# Div4RX5808-PRO_MB_V1_2.net
KiCad netlist of a schematic drawn in EAGLE
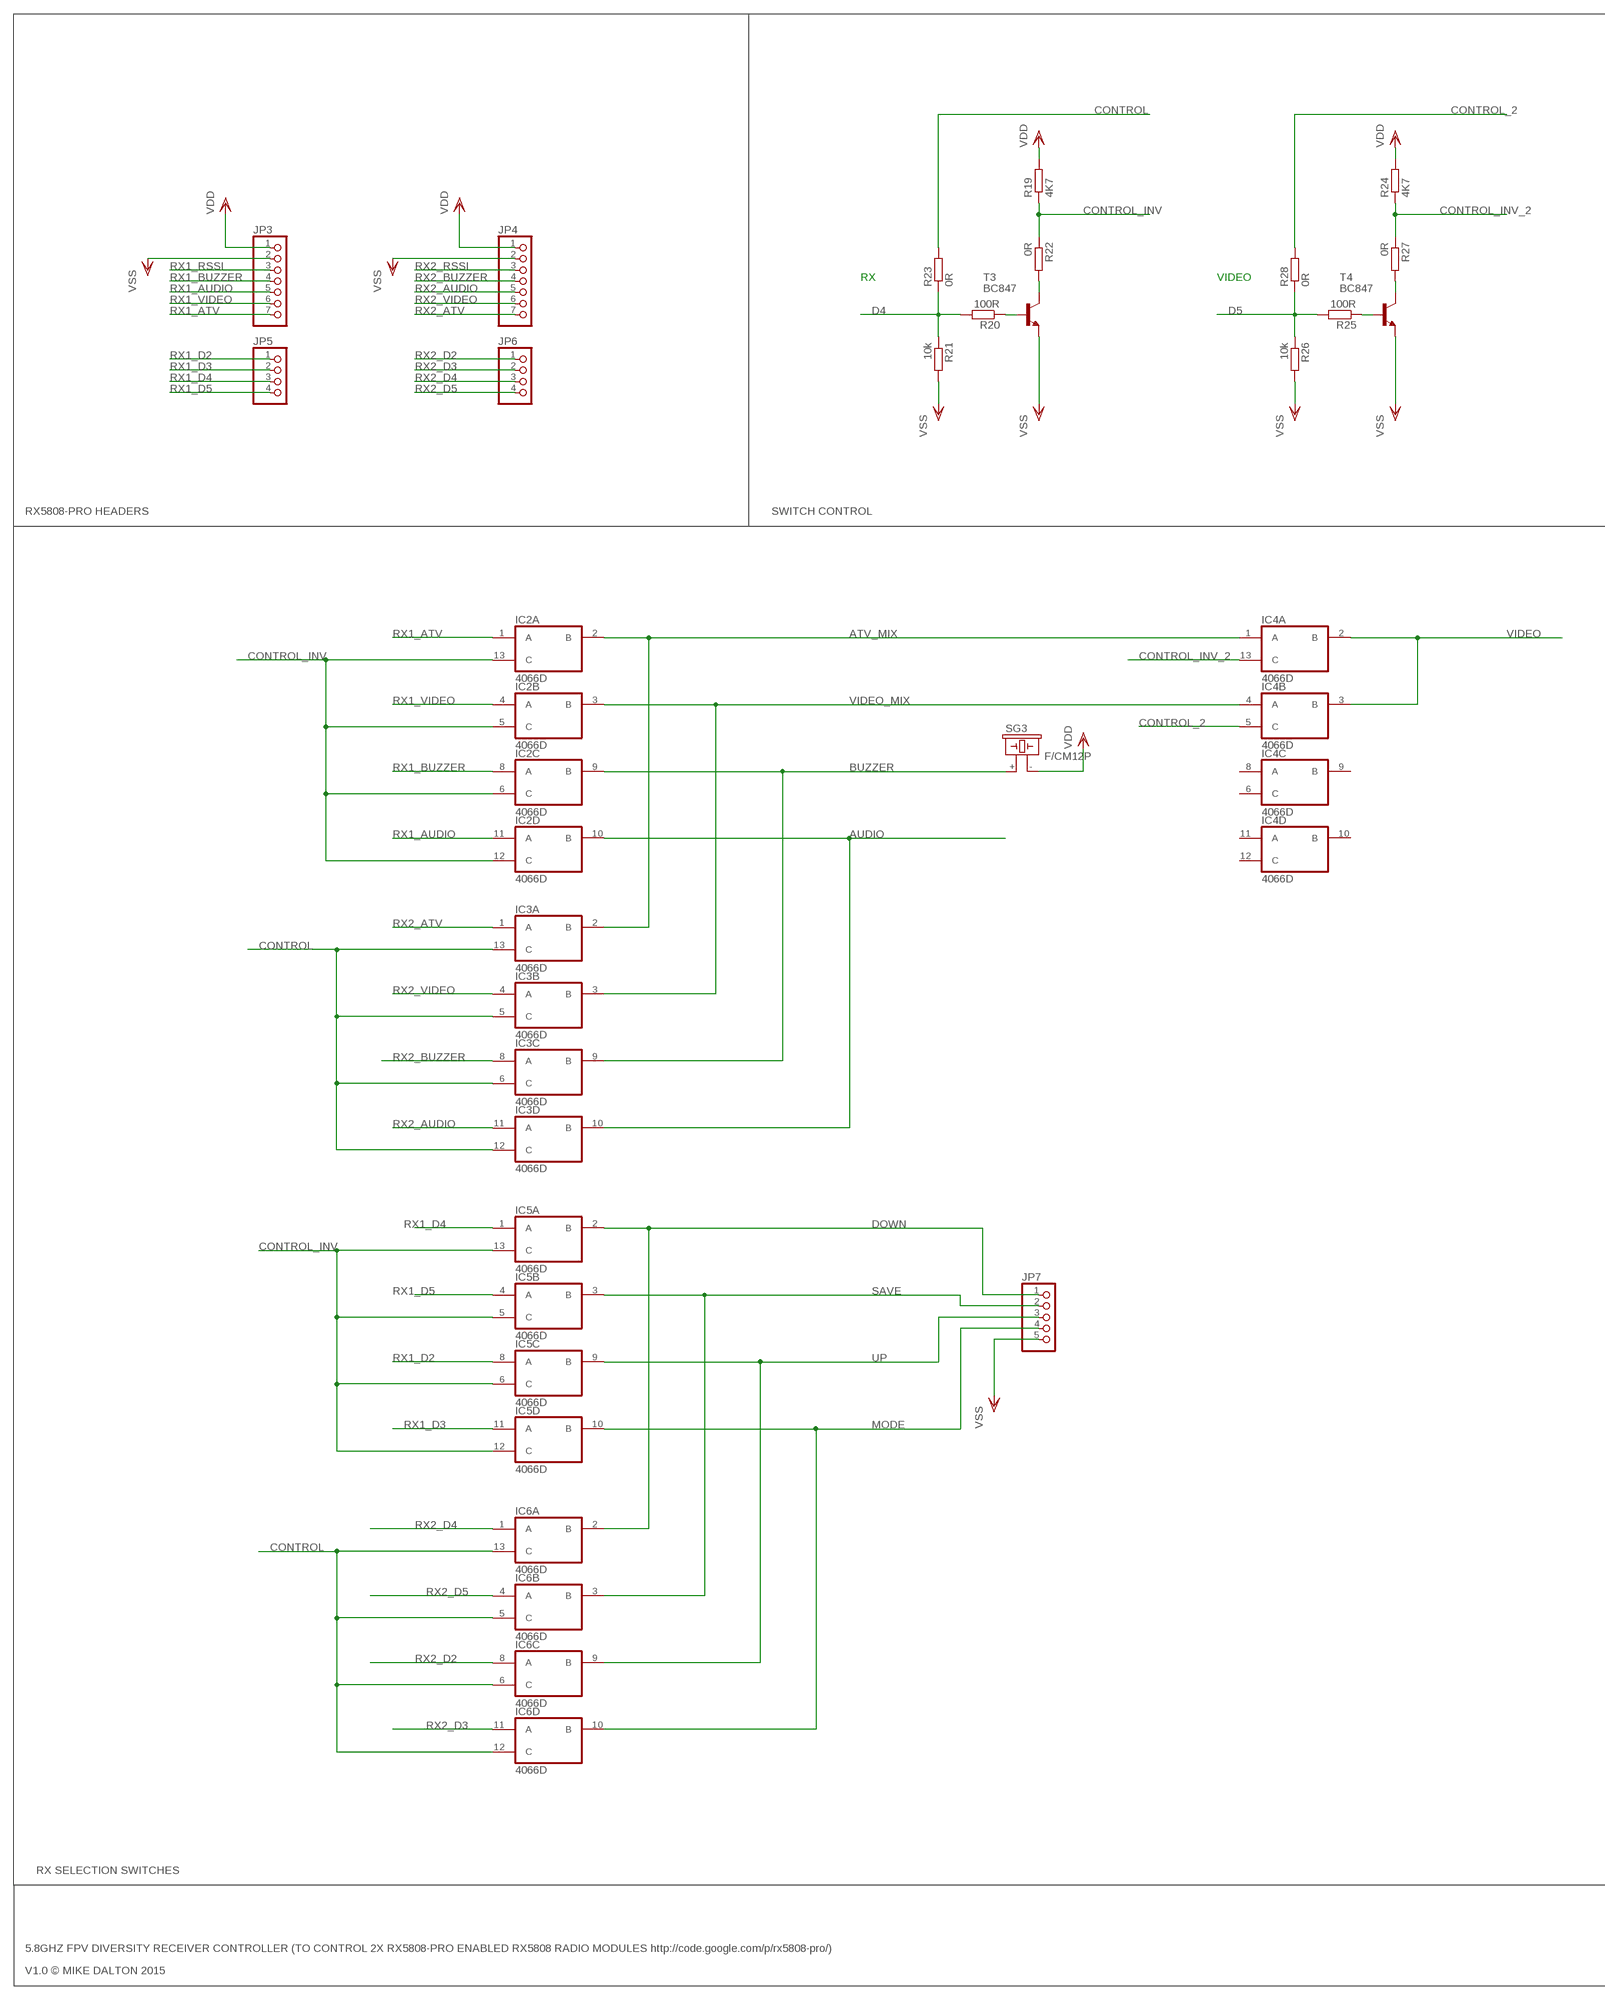
[diagram p0: schematic, sheet 1, part 1 of 2]
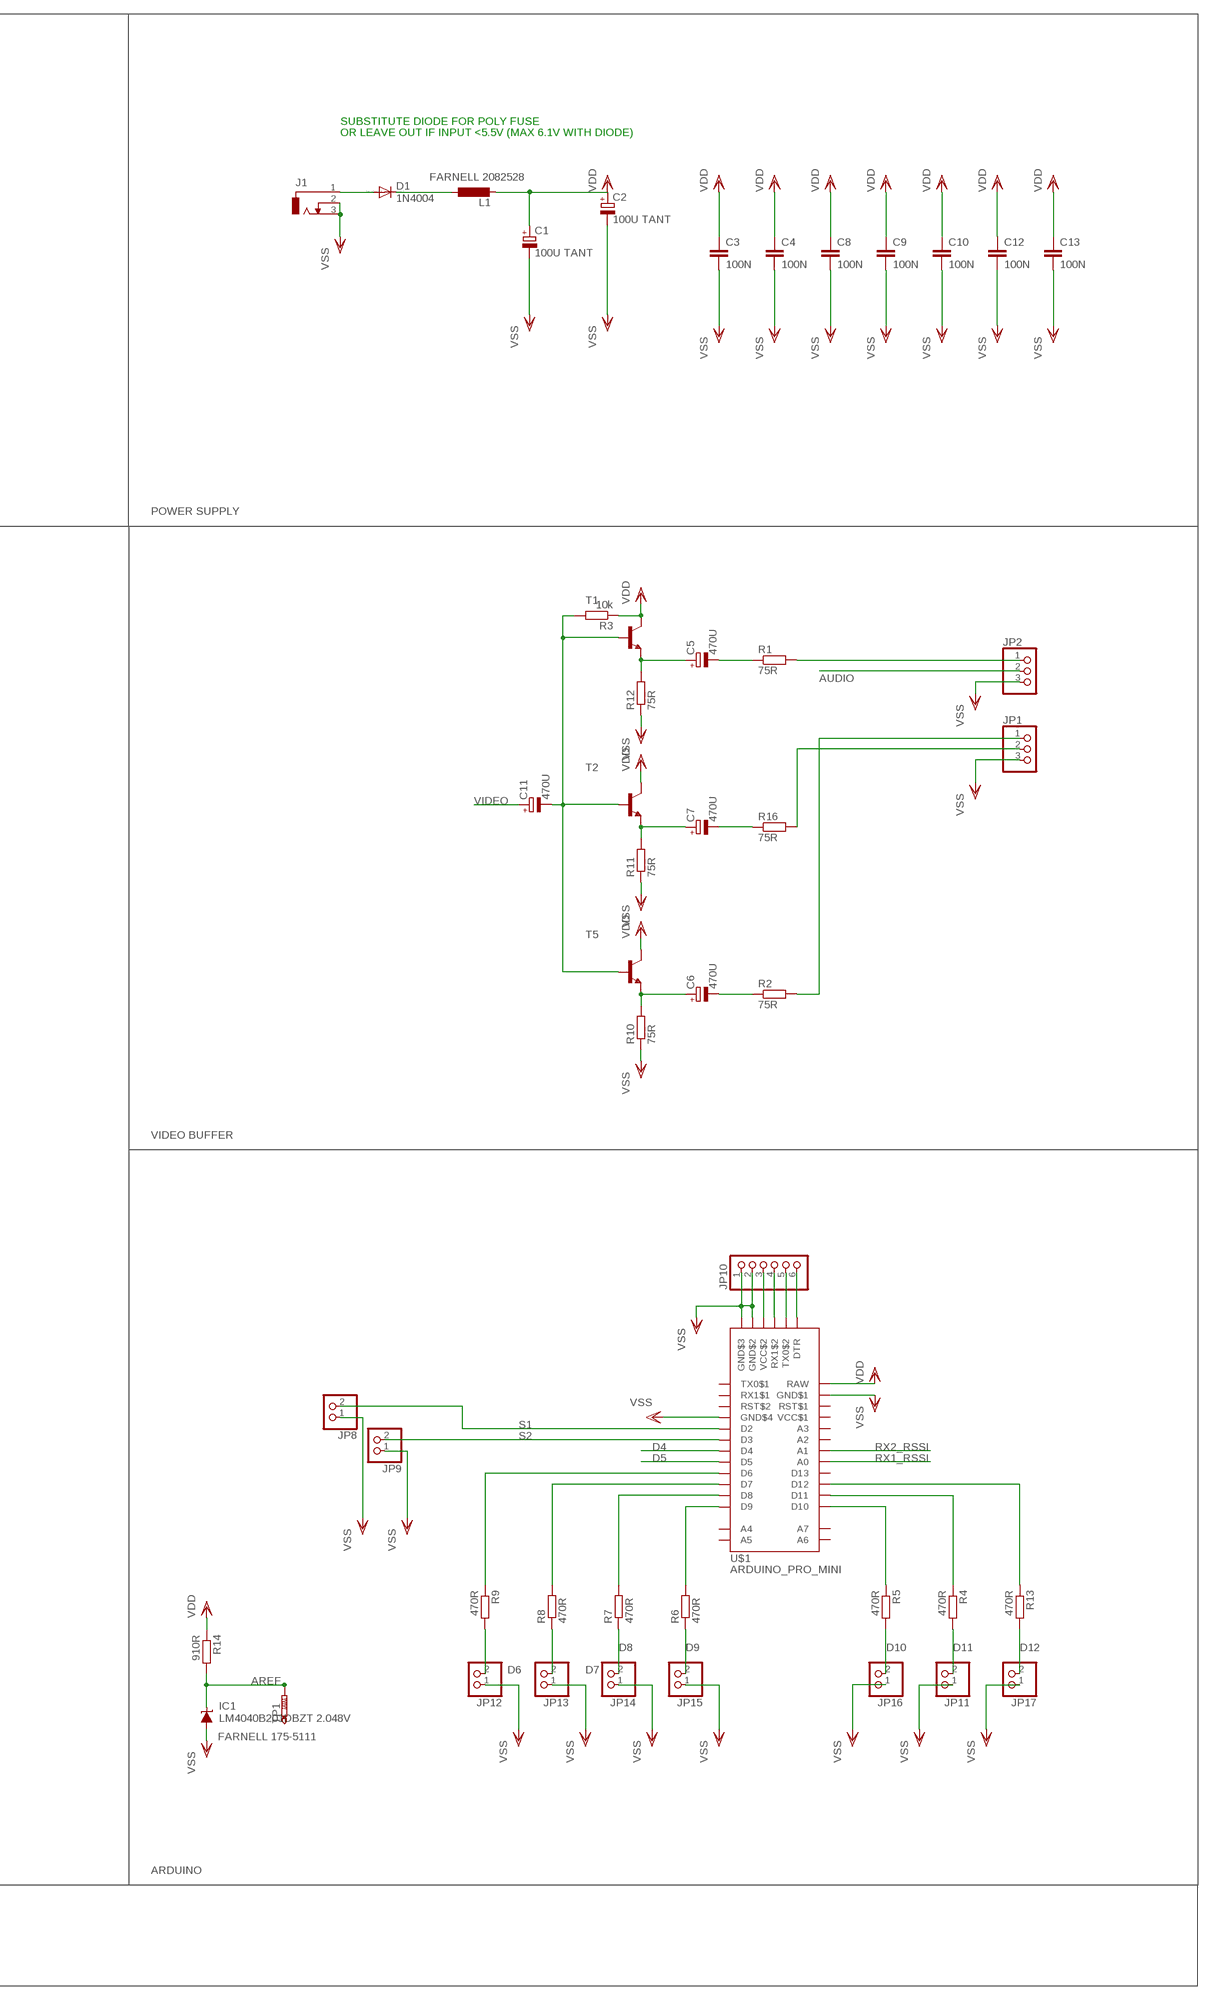
[diagram p1: schematic, sheet 1, part 2 of 2]

(export (version "E")
  (design (tool "Eeschema 10.0.6"))
  (components
    (comp (ref "C1")
      (value "100U TANT")
      (footprint "eagle-import:C_6032-28R")
      (libsource (lib "eagle-import") (part "CPOL-EUC/6032-28R"))
    )
    (comp (ref "C2")
      (value "100U TANT")
      (footprint "eagle-import:C_6032-28R")
      (libsource (lib "eagle-import") (part "CPOL-EUC/6032-28R"))
    )
    (comp (ref "C3")
      (value "100N")
      (footprint "eagle-import:C0603")
      (libsource (lib "eagle-import") (part "C-EUC0603"))
    )
    (comp (ref "C4")
      (value "100N")
      (footprint "eagle-import:C0603")
      (libsource (lib "eagle-import") (part "C-EUC0603"))
    )
    (comp (ref "C5")
      (value "470U")
      (footprint "eagle-import:E5-10,5")
      (libsource (lib "eagle-import") (part "CPOL-EUE5-10.5"))
    )
    (comp (ref "C6")
      (value "470U")
      (footprint "eagle-import:E5-10,5")
      (libsource (lib "eagle-import") (part "CPOL-EUE5-10.5"))
    )
    (comp (ref "C7")
      (value "470U")
      (footprint "eagle-import:E5-10,5")
      (libsource (lib "eagle-import") (part "CPOL-EUE5-10.5"))
    )
    (comp (ref "C8")
      (value "100N")
      (footprint "eagle-import:C0603")
      (libsource (lib "eagle-import") (part "C-EUC0603"))
    )
    (comp (ref "C9")
      (value "100N")
      (footprint "eagle-import:C0603")
      (libsource (lib "eagle-import") (part "C-EUC0603"))
    )
    (comp (ref "C10")
      (value "100N")
      (footprint "eagle-import:C0603")
      (libsource (lib "eagle-import") (part "C-EUC0603"))
    )
    (comp (ref "C11")
      (value "470U")
      (footprint "eagle-import:E5-10,5")
      (libsource (lib "eagle-import") (part "CPOL-EUE5-10.5"))
    )
    (comp (ref "C12")
      (value "100N")
      (footprint "eagle-import:C0603")
      (libsource (lib "eagle-import") (part "C-EUC0603"))
    )
    (comp (ref "C13")
      (value "100N")
      (footprint "eagle-import:C0603")
      (libsource (lib "eagle-import") (part "C-EUC0603"))
    )
    (comp (ref "D1")
      (value "1N4004")
      (footprint "eagle-import:DO41-10")
      (libsource (lib "eagle-import") (part "1N4004"))
    )
    (comp (ref "IC1")
      (value "LM4040B201DBZT 2.048V")
      (footprint "eagle-import:DBZ_R-PDSO-G3")
      (fields (field (name "MPN") "LM4041A12IDBZR"))
      (libsource (lib "eagle-import") (part "LM4041DBZA12"))
    )
    (comp (ref "IC2")
      (value "4066D")
      (footprint "eagle-import:SO14")
      (libsource (lib "eagle-import") (part "4066D"))
    )
    (comp (ref "IC3")
      (value "4066D")
      (footprint "eagle-import:SO14")
      (libsource (lib "eagle-import") (part "4066D"))
    )
    (comp (ref "IC4")
      (value "4066D")
      (footprint "eagle-import:SO14")
      (libsource (lib "eagle-import") (part "4066D"))
    )
    (comp (ref "IC5")
      (value "4066D")
      (footprint "eagle-import:SO14")
      (libsource (lib "eagle-import") (part "4066D"))
    )
    (comp (ref "IC6")
      (value "4066D")
      (footprint "eagle-import:SO14")
      (libsource (lib "eagle-import") (part "4066D"))
    )
    (comp (ref "J1")
      (value "DCJ0303")
      (footprint "eagle-import:DCJ0303")
      (libsource (lib "eagle-import") (part "DCJ0303"))
    )
    (comp (ref "JP1")
      (value "PINHD-1X3")
      (footprint "eagle-import:1X03")
      (libsource (lib "eagle-import") (part "PINHD-1X3"))
    )
    (comp (ref "JP2")
      (value "PINHD-1X3")
      (footprint "eagle-import:1X03")
      (libsource (lib "eagle-import") (part "PINHD-1X3"))
    )
    (comp (ref "JP3")
      (value "PINHD-1X7")
      (footprint "eagle-import:1X07")
      (libsource (lib "eagle-import") (part "PINHD-1X7"))
    )
    (comp (ref "JP4")
      (value "PINHD-1X7")
      (footprint "eagle-import:1X07")
      (libsource (lib "eagle-import") (part "PINHD-1X7"))
    )
    (comp (ref "JP5")
      (value "PINHD-1X4")
      (footprint "eagle-import:1X04")
      (libsource (lib "eagle-import") (part "PINHD-1X4"))
    )
    (comp (ref "JP6")
      (value "PINHD-1X4")
      (footprint "eagle-import:1X04")
      (libsource (lib "eagle-import") (part "PINHD-1X4"))
    )
    (comp (ref "JP7")
      (value "PINHD-1X5")
      (footprint "eagle-import:1X05")
      (libsource (lib "eagle-import") (part "PINHD-1X5"))
    )
    (comp (ref "JP8")
      (value "PINHD-1X2")
      (footprint "eagle-import:1X02")
      (libsource (lib "eagle-import") (part "PINHD-1X2"))
    )
    (comp (ref "JP9")
      (value "PINHD-1X2")
      (footprint "eagle-import:1X02")
      (libsource (lib "eagle-import") (part "PINHD-1X2"))
    )
    (comp (ref "JP10")
      (value "PINHD-1X6")
      (footprint "eagle-import:1X06")
      (libsource (lib "eagle-import") (part "PINHD-1X6"))
    )
    (comp (ref "JP11")
      (value "PINHD-1X2")
      (footprint "eagle-import:1X02")
      (libsource (lib "eagle-import") (part "PINHD-1X2"))
    )
    (comp (ref "JP12")
      (value "PINHD-1X2")
      (footprint "eagle-import:1X02")
      (libsource (lib "eagle-import") (part "PINHD-1X2"))
    )
    (comp (ref "JP13")
      (value "PINHD-1X2")
      (footprint "eagle-import:1X02")
      (libsource (lib "eagle-import") (part "PINHD-1X2"))
    )
    (comp (ref "JP14")
      (value "PINHD-1X2")
      (footprint "eagle-import:1X02")
      (libsource (lib "eagle-import") (part "PINHD-1X2"))
    )
    (comp (ref "JP15")
      (value "PINHD-1X2")
      (footprint "eagle-import:1X02")
      (libsource (lib "eagle-import") (part "PINHD-1X2"))
    )
    (comp (ref "JP16")
      (value "PINHD-1X2")
      (footprint "eagle-import:1X02")
      (libsource (lib "eagle-import") (part "PINHD-1X2"))
    )
    (comp (ref "JP17")
      (value "PINHD-1X2")
      (footprint "eagle-import:1X02")
      (libsource (lib "eagle-import") (part "PINHD-1X2"))
    )
    (comp (ref "L1")
      (value "L-EU0207/7")
      (footprint "eagle-import:0207_7")
      (libsource (lib "eagle-import") (part "L-EU0207/7"))
    )
    (comp (ref "R1")
      (value "75R")
      (footprint "eagle-import:M0805")
      (libsource (lib "eagle-import") (part "R-EU_M0805"))
    )
    (comp (ref "R2")
      (value "75R")
      (footprint "eagle-import:M0805")
      (libsource (lib "eagle-import") (part "R-EU_M0805"))
    )
    (comp (ref "R3")
      (value "10k")
      (footprint "eagle-import:M0805")
      (libsource (lib "eagle-import") (part "R-EU_M0805"))
    )
    (comp (ref "R4")
      (value "470R")
      (footprint "eagle-import:R0603")
      (libsource (lib "eagle-import") (part "R-EU_R0603"))
    )
    (comp (ref "R5")
      (value "470R")
      (footprint "eagle-import:R0603")
      (libsource (lib "eagle-import") (part "R-EU_R0603"))
    )
    (comp (ref "R6")
      (value "470R")
      (footprint "eagle-import:R0603")
      (libsource (lib "eagle-import") (part "R-EU_R0603"))
    )
    (comp (ref "R7")
      (value "470R")
      (footprint "eagle-import:R0603")
      (libsource (lib "eagle-import") (part "R-EU_R0603"))
    )
    (comp (ref "R8")
      (value "470R")
      (footprint "eagle-import:R0603")
      (libsource (lib "eagle-import") (part "R-EU_R0603"))
    )
    (comp (ref "R9")
      (value "470R")
      (footprint "eagle-import:R0603")
      (libsource (lib "eagle-import") (part "R-EU_R0603"))
    )
    (comp (ref "R10")
      (value "75R")
      (footprint "eagle-import:M0805")
      (libsource (lib "eagle-import") (part "R-EU_M0805"))
    )
    (comp (ref "R11")
      (value "75R")
      (footprint "eagle-import:M0805")
      (libsource (lib "eagle-import") (part "R-EU_M0805"))
    )
    (comp (ref "R12")
      (value "75R")
      (footprint "eagle-import:M0805")
      (libsource (lib "eagle-import") (part "R-EU_M0805"))
    )
    (comp (ref "R13")
      (value "470R")
      (footprint "eagle-import:R0603")
      (libsource (lib "eagle-import") (part "R-EU_R0603"))
    )
    (comp (ref "R14")
      (value "910R")
      (footprint "eagle-import:R0603")
      (libsource (lib "eagle-import") (part "R-EU_R0603"))
    )
    (comp (ref "R16")
      (value "75R")
      (footprint "eagle-import:M0805")
      (libsource (lib "eagle-import") (part "R-EU_M0805"))
    )
    (comp (ref "R19")
      (value "4K7")
      (footprint "eagle-import:M0805")
      (libsource (lib "eagle-import") (part "R-EU_M0805"))
    )
    (comp (ref "R20")
      (value "100R")
      (footprint "eagle-import:M0805")
      (libsource (lib "eagle-import") (part "R-EU_M0805"))
    )
    (comp (ref "R21")
      (value "10k")
      (footprint "eagle-import:M0805")
      (libsource (lib "eagle-import") (part "R-EU_M0805"))
    )
    (comp (ref "R22")
      (value "0R")
      (footprint "eagle-import:M0805")
      (libsource (lib "eagle-import") (part "R-EU_M0805"))
    )
    (comp (ref "R23")
      (value "0R")
      (footprint "eagle-import:M0805")
      (libsource (lib "eagle-import") (part "R-EU_M0805"))
    )
    (comp (ref "R24")
      (value "4K7")
      (footprint "eagle-import:M0805")
      (libsource (lib "eagle-import") (part "R-EU_M0805"))
    )
    (comp (ref "R25")
      (value "100R")
      (footprint "eagle-import:M0805")
      (libsource (lib "eagle-import") (part "R-EU_M0805"))
    )
    (comp (ref "R26")
      (value "10k")
      (footprint "eagle-import:M0805")
      (libsource (lib "eagle-import") (part "R-EU_M0805"))
    )
    (comp (ref "R27")
      (value "0R")
      (footprint "eagle-import:M0805")
      (libsource (lib "eagle-import") (part "R-EU_M0805"))
    )
    (comp (ref "R28")
      (value "0R")
      (footprint "eagle-import:M0805")
      (libsource (lib "eagle-import") (part "R-EU_M0805"))
    )
    (comp (ref "SG3")
      (value "F/CM12P")
      (footprint "eagle-import:F_CM12P")
      (libsource (lib "eagle-import") (part "F/CM12P"))
    )
    (comp (ref "T1")
      (value "MMBT2222ALT1-NPN-SOT23-BEC")
      (footprint "eagle-import:SOT23-BEC")
      (libsource (lib "eagle-import") (part "transistor-neu-to92_-NPN-SOT23-BECMMBT2222ALT1"))
    )
    (comp (ref "T2")
      (value "MMBT2222ALT1-NPN-SOT23-BEC")
      (footprint "eagle-import:SOT23-BEC")
      (libsource (lib "eagle-import") (part "transistor-neu-to92_-NPN-SOT23-BECMMBT2222ALT1"))
    )
    (comp (ref "T3")
      (value "BC847")
      (footprint "eagle-import:SOT23-BEC")
      (libsource (lib "eagle-import") (part "-NPN-SOT23-BECBC847B"))
    )
    (comp (ref "T4")
      (value "BC847")
      (footprint "eagle-import:SOT23-BEC")
      (libsource (lib "eagle-import") (part "-NPN-SOT23-BECBC847B"))
    )
    (comp (ref "T5")
      (value "MMBT2222ALT1-NPN-SOT23-BEC")
      (footprint "eagle-import:SOT23-BEC")
      (libsource (lib "eagle-import") (part "transistor-neu-to92_-NPN-SOT23-BECMMBT2222ALT1"))
    )
    (comp (ref "TP1")
      (value "PTR1TP20SQ")
      (footprint "eagle-import:TP20SQ")
      (libsource (lib "eagle-import") (part "PTR1TP20SQ"))
    )
    (comp (ref "U$1")
      (value "ARDUINO_PRO_MINI")
      (footprint "eagle-import:ARDUINO_PRO_MINI")
      (libsource (lib "eagle-import") (part "ARDUINO_PRO_MINI"))
    )
  )
  (nets
    (net (code "1") (name "/AREF") (class "Default")
      (node (ref "IC1") (pin "1") (pinfunction "C_1") (pintype "passive"))
      (node (ref "R14") (pin "2") (pinfunction "2_2") (pintype "passive"))
      (node (ref "TP1") (pin "TP") (pinfunction "TP_TP") (pintype "input"))
    )
    (net (code "2") (name "/ATV_MIX") (class "Default")
      (node (ref "IC2") (pin "2") (pinfunction "B_2") (pintype "tri_state"))
      (node (ref "IC3") (pin "2") (pinfunction "B_2") (pintype "tri_state"))
      (node (ref "IC4") (pin "1") (pinfunction "A_1") (pintype "tri_state"))
    )
    (net (code "3") (name "/AUDIO") (class "Default")
      (node (ref "IC2") (pin "10") (pinfunction "B_10") (pintype "tri_state"))
      (node (ref "IC3") (pin "10") (pinfunction "B_10") (pintype "tri_state"))
      (node (ref "JP2") (pin "2") (pinfunction "2_2") (pintype "passive"))
    )
    (net (code "4") (name "/BUZZER") (class "Default")
      (node (ref "IC2") (pin "9") (pinfunction "B_9") (pintype "tri_state"))
      (node (ref "IC3") (pin "9") (pinfunction "B_9") (pintype "tri_state"))
      (node (ref "SG3") (pin "+") (pinfunction "1_+") (pintype "passive"))
    )
    (net (code "5") (name "/CONTROL") (class "Default")
      (node (ref "IC3") (pin "12") (pinfunction "C_12") (pintype "input"))
      (node (ref "IC3") (pin "13") (pinfunction "C_13") (pintype "input"))
      (node (ref "IC3") (pin "5") (pinfunction "C_5") (pintype "input"))
      (node (ref "IC3") (pin "6") (pinfunction "C_6") (pintype "input"))
      (node (ref "IC6") (pin "12") (pinfunction "C_12") (pintype "input"))
      (node (ref "IC6") (pin "13") (pinfunction "C_13") (pintype "input"))
      (node (ref "IC6") (pin "5") (pinfunction "C_5") (pintype "input"))
      (node (ref "IC6") (pin "6") (pinfunction "C_6") (pintype "input"))
      (node (ref "R23") (pin "2") (pinfunction "2_2") (pintype "passive"))
    )
    (net (code "6") (name "/CONTROL_2") (class "Default")
      (node (ref "IC4") (pin "5") (pinfunction "C_5") (pintype "input"))
      (node (ref "R28") (pin "2") (pinfunction "2_2") (pintype "passive"))
    )
    (net (code "7") (name "/CONTROL_INV") (class "Default")
      (node (ref "IC2") (pin "12") (pinfunction "C_12") (pintype "input"))
      (node (ref "IC2") (pin "13") (pinfunction "C_13") (pintype "input"))
      (node (ref "IC2") (pin "5") (pinfunction "C_5") (pintype "input"))
      (node (ref "IC2") (pin "6") (pinfunction "C_6") (pintype "input"))
      (node (ref "IC5") (pin "12") (pinfunction "C_12") (pintype "input"))
      (node (ref "IC5") (pin "13") (pinfunction "C_13") (pintype "input"))
      (node (ref "IC5") (pin "5") (pinfunction "C_5") (pintype "input"))
      (node (ref "IC5") (pin "6") (pinfunction "C_6") (pintype "input"))
      (node (ref "R19") (pin "1") (pinfunction "1_1") (pintype "passive"))
      (node (ref "R22") (pin "1") (pinfunction "1_1") (pintype "passive"))
    )
    (net (code "8") (name "/CONTROL_INV_2") (class "Default")
      (node (ref "IC4") (pin "13") (pinfunction "C_13") (pintype "input"))
      (node (ref "R24") (pin "1") (pinfunction "1_1") (pintype "passive"))
      (node (ref "R27") (pin "1") (pinfunction "1_1") (pintype "passive"))
    )
    (net (code "9") (name "/D4") (class "Default")
      (node (ref "R20") (pin "2") (pinfunction "2_2") (pintype "passive"))
      (node (ref "R21") (pin "1") (pinfunction "1_1") (pintype "passive"))
      (node (ref "R23") (pin "1") (pinfunction "1_1") (pintype "passive"))
      (node (ref "U$1") (pin "D4") (pinfunction "D4_D4") (pintype "bidirectional"))
    )
    (net (code "10") (name "/D5") (class "Default")
      (node (ref "R25") (pin "2") (pinfunction "2_2") (pintype "passive"))
      (node (ref "R26") (pin "1") (pinfunction "1_1") (pintype "passive"))
      (node (ref "R28") (pin "1") (pinfunction "1_1") (pintype "passive"))
      (node (ref "U$1") (pin "D5") (pinfunction "D5_D5") (pintype "bidirectional"))
    )
    (net (code "11") (name "/D6") (class "Default")
      (node (ref "JP12") (pin "2") (pinfunction "2_2") (pintype "passive"))
      (node (ref "R9") (pin "2") (pinfunction "2_2") (pintype "passive"))
    )
    (net (code "12") (name "/D7") (class "Default")
      (node (ref "JP13") (pin "2") (pinfunction "2_2") (pintype "passive"))
      (node (ref "R8") (pin "1") (pinfunction "1_1") (pintype "passive"))
    )
    (net (code "13") (name "/D8") (class "Default")
      (node (ref "JP14") (pin "2") (pinfunction "2_2") (pintype "passive"))
      (node (ref "R7") (pin "1") (pinfunction "1_1") (pintype "passive"))
    )
    (net (code "14") (name "/D9") (class "Default")
      (node (ref "JP15") (pin "2") (pinfunction "2_2") (pintype "passive"))
      (node (ref "R6") (pin "1") (pinfunction "1_1") (pintype "passive"))
    )
    (net (code "15") (name "/D10") (class "Default")
      (node (ref "JP16") (pin "2") (pinfunction "2_2") (pintype "passive"))
      (node (ref "R5") (pin "2") (pinfunction "2_2") (pintype "passive"))
    )
    (net (code "16") (name "/D11") (class "Default")
      (node (ref "JP11") (pin "2") (pinfunction "2_2") (pintype "passive"))
      (node (ref "R4") (pin "2") (pinfunction "2_2") (pintype "passive"))
    )
    (net (code "17") (name "/D12") (class "Default")
      (node (ref "JP17") (pin "2") (pinfunction "2_2") (pintype "passive"))
      (node (ref "R13") (pin "2") (pinfunction "2_2") (pintype "passive"))
    )
    (net (code "18") (name "/DOWN") (class "Default")
      (node (ref "IC5") (pin "2") (pinfunction "B_2") (pintype "tri_state"))
      (node (ref "IC6") (pin "2") (pinfunction "B_2") (pintype "tri_state"))
      (node (ref "JP7") (pin "1") (pinfunction "1_1") (pintype "passive"))
    )
    (net (code "19") (name "/MODE") (class "Default")
      (node (ref "IC5") (pin "10") (pinfunction "B_10") (pintype "tri_state"))
      (node (ref "IC6") (pin "10") (pinfunction "B_10") (pintype "tri_state"))
      (node (ref "JP7") (pin "4") (pinfunction "4_4") (pintype "passive"))
    )
    (net (code "20") (name "/RX1_ATV") (class "Default")
      (node (ref "IC2") (pin "1") (pinfunction "A_1") (pintype "tri_state"))
      (node (ref "JP3") (pin "7") (pinfunction "7_7") (pintype "passive"))
    )
    (net (code "21") (name "/RX1_AUDIO") (class "Default")
      (node (ref "IC2") (pin "11") (pinfunction "A_11") (pintype "tri_state"))
      (node (ref "JP3") (pin "5") (pinfunction "5_5") (pintype "passive"))
    )
    (net (code "22") (name "/RX1_BUZZER") (class "Default")
      (node (ref "IC2") (pin "8") (pinfunction "A_8") (pintype "tri_state"))
      (node (ref "JP3") (pin "4") (pinfunction "4_4") (pintype "passive"))
    )
    (net (code "23") (name "/RX1_D2") (class "Default")
      (node (ref "IC5") (pin "8") (pinfunction "A_8") (pintype "tri_state"))
      (node (ref "JP5") (pin "1") (pinfunction "1_1") (pintype "passive"))
    )
    (net (code "24") (name "/RX1_D3") (class "Default")
      (node (ref "IC5") (pin "11") (pinfunction "A_11") (pintype "tri_state"))
      (node (ref "JP5") (pin "2") (pinfunction "2_2") (pintype "passive"))
    )
    (net (code "25") (name "/RX1_D4") (class "Default")
      (node (ref "IC5") (pin "1") (pinfunction "A_1") (pintype "tri_state"))
      (node (ref "JP5") (pin "3") (pinfunction "3_3") (pintype "passive"))
    )
    (net (code "26") (name "/RX1_D5") (class "Default")
      (node (ref "IC5") (pin "4") (pinfunction "A_4") (pintype "tri_state"))
      (node (ref "JP5") (pin "4") (pinfunction "4_4") (pintype "passive"))
    )
    (net (code "27") (name "/RX1_RSSI") (class "Default")
      (node (ref "JP3") (pin "3") (pinfunction "3_3") (pintype "passive"))
      (node (ref "U$1") (pin "A0") (pinfunction "A0_A0") (pintype "bidirectional"))
    )
    (net (code "28") (name "/RX1_VIDEO") (class "Default")
      (node (ref "IC2") (pin "4") (pinfunction "A_4") (pintype "tri_state"))
      (node (ref "JP3") (pin "6") (pinfunction "6_6") (pintype "passive"))
    )
    (net (code "29") (name "/RX2_ATV") (class "Default")
      (node (ref "IC3") (pin "1") (pinfunction "A_1") (pintype "tri_state"))
      (node (ref "JP4") (pin "7") (pinfunction "7_7") (pintype "passive"))
    )
    (net (code "30") (name "/RX2_AUDIO") (class "Default")
      (node (ref "IC3") (pin "11") (pinfunction "A_11") (pintype "tri_state"))
      (node (ref "JP4") (pin "5") (pinfunction "5_5") (pintype "passive"))
    )
    (net (code "31") (name "/RX2_BUZZER") (class "Default")
      (node (ref "IC3") (pin "8") (pinfunction "A_8") (pintype "tri_state"))
      (node (ref "JP4") (pin "4") (pinfunction "4_4") (pintype "passive"))
    )
    (net (code "32") (name "/RX2_D2") (class "Default")
      (node (ref "IC6") (pin "8") (pinfunction "A_8") (pintype "tri_state"))
      (node (ref "JP6") (pin "1") (pinfunction "1_1") (pintype "passive"))
    )
    (net (code "33") (name "/RX2_D3") (class "Default")
      (node (ref "IC6") (pin "11") (pinfunction "A_11") (pintype "tri_state"))
      (node (ref "JP6") (pin "2") (pinfunction "2_2") (pintype "passive"))
    )
    (net (code "34") (name "/RX2_D4") (class "Default")
      (node (ref "IC6") (pin "1") (pinfunction "A_1") (pintype "tri_state"))
      (node (ref "JP6") (pin "3") (pinfunction "3_3") (pintype "passive"))
    )
    (net (code "35") (name "/RX2_D5") (class "Default")
      (node (ref "IC6") (pin "4") (pinfunction "A_4") (pintype "tri_state"))
      (node (ref "JP6") (pin "4") (pinfunction "4_4") (pintype "passive"))
    )
    (net (code "36") (name "/RX2_RSSI") (class "Default")
      (node (ref "JP4") (pin "3") (pinfunction "3_3") (pintype "passive"))
      (node (ref "U$1") (pin "A1") (pinfunction "A1_A1") (pintype "bidirectional"))
    )
    (net (code "37") (name "/RX2_VIDEO") (class "Default")
      (node (ref "IC3") (pin "4") (pinfunction "A_4") (pintype "tri_state"))
      (node (ref "JP4") (pin "6") (pinfunction "6_6") (pintype "passive"))
    )
    (net (code "38") (name "/S1") (class "Default")
      (node (ref "JP8") (pin "2") (pinfunction "2_2") (pintype "passive"))
      (node (ref "U$1") (pin "D2") (pinfunction "D2_D2") (pintype "bidirectional"))
    )
    (net (code "39") (name "/S2") (class "Default")
      (node (ref "JP9") (pin "2") (pinfunction "2_2") (pintype "passive"))
      (node (ref "U$1") (pin "D3") (pinfunction "D3_D3") (pintype "bidirectional"))
    )
    (net (code "40") (name "/SAVE") (class "Default")
      (node (ref "IC5") (pin "3") (pinfunction "B_3") (pintype "tri_state"))
      (node (ref "IC6") (pin "3") (pinfunction "B_3") (pintype "tri_state"))
      (node (ref "JP7") (pin "2") (pinfunction "2_2") (pintype "passive"))
    )
    (net (code "41") (name "/UP") (class "Default")
      (node (ref "IC5") (pin "9") (pinfunction "B_9") (pintype "tri_state"))
      (node (ref "IC6") (pin "9") (pinfunction "B_9") (pintype "tri_state"))
      (node (ref "JP7") (pin "3") (pinfunction "3_3") (pintype "passive"))
    )
    (net (code "42") (name "/VCC$1") (class "Default")
      (node (ref "U$1") (pin "VCC$1") (pinfunction "VCC$1_VCC$1") (pintype "power_in"))
    )
    (net (code "43") (name "/VIDEO") (class "Default")
      (node (ref "C11") (pin "+") (pinfunction "+_+") (pintype "passive"))
      (node (ref "IC4") (pin "2") (pinfunction "B_2") (pintype "tri_state"))
      (node (ref "IC4") (pin "3") (pinfunction "B_3") (pintype "tri_state"))
    )
    (net (code "44") (name "/VIDEO_MIX") (class "Default")
      (node (ref "IC2") (pin "3") (pinfunction "B_3") (pintype "tri_state"))
      (node (ref "IC3") (pin "3") (pinfunction "B_3") (pintype "tri_state"))
      (node (ref "IC4") (pin "4") (pinfunction "A_4") (pintype "tri_state"))
    )
    (net (code "45") (name "Net-(C5-Pad+)") (class "Default")
      (node (ref "C5") (pin "+") (pinfunction "+_+") (pintype "passive"))
      (node (ref "R12") (pin "2") (pinfunction "2_2") (pintype "passive"))
      (node (ref "T1") (pin "E") (pinfunction "E_E") (pintype "passive"))
    )
    (net (code "46") (name "Net-(C5-Pad-)") (class "Default")
      (node (ref "C5") (pin "-") (pinfunction "-_-") (pintype "passive"))
      (node (ref "R1") (pin "1") (pinfunction "1_1") (pintype "passive"))
    )
    (net (code "47") (name "Net-(C6-Pad+)") (class "Default")
      (node (ref "C6") (pin "+") (pinfunction "+_+") (pintype "passive"))
      (node (ref "R10") (pin "2") (pinfunction "2_2") (pintype "passive"))
      (node (ref "T5") (pin "E") (pinfunction "E_E") (pintype "passive"))
    )
    (net (code "48") (name "Net-(C6-Pad-)") (class "Default")
      (node (ref "C6") (pin "-") (pinfunction "-_-") (pintype "passive"))
      (node (ref "R2") (pin "1") (pinfunction "1_1") (pintype "passive"))
    )
    (net (code "49") (name "Net-(C7-Pad+)") (class "Default")
      (node (ref "C7") (pin "+") (pinfunction "+_+") (pintype "passive"))
      (node (ref "R11") (pin "2") (pinfunction "2_2") (pintype "passive"))
      (node (ref "T2") (pin "E") (pinfunction "E_E") (pintype "passive"))
    )
    (net (code "50") (name "Net-(C7-Pad-)") (class "Default")
      (node (ref "C7") (pin "-") (pinfunction "-_-") (pintype "passive"))
      (node (ref "R16") (pin "1") (pinfunction "1_1") (pintype "passive"))
    )
    (net (code "51") (name "Net-(C11-Pad-)") (class "Default")
      (node (ref "C11") (pin "-") (pinfunction "-_-") (pintype "passive"))
      (node (ref "R3") (pin "2") (pinfunction "2_2") (pintype "passive"))
      (node (ref "T1") (pin "B") (pinfunction "B_B") (pintype "passive"))
      (node (ref "T2") (pin "B") (pinfunction "B_B") (pintype "passive"))
      (node (ref "T5") (pin "B") (pinfunction "B_B") (pintype "passive"))
    )
    (net (code "52") (name "Net-(D1-PadA)") (class "Default")
      (node (ref "D1") (pin "A") (pinfunction "A_A") (pintype "passive"))
      (node (ref "J1") (pin "1") (pinfunction "1_1") (pintype "passive"))
    )
    (net (code "53") (name "Net-(D1-PadC)") (class "Default")
      (node (ref "D1") (pin "C") (pinfunction "C_C") (pintype "passive"))
      (node (ref "L1") (pin "1") (pinfunction "1_1") (pintype "passive"))
    )
    (net (code "54") (name "Net-(JP1-Pad1)") (class "Default")
      (node (ref "JP1") (pin "1") (pinfunction "1_1") (pintype "passive"))
      (node (ref "R2") (pin "2") (pinfunction "2_2") (pintype "passive"))
    )
    (net (code "55") (name "Net-(JP1-Pad2)") (class "Default")
      (node (ref "JP1") (pin "2") (pinfunction "2_2") (pintype "passive"))
      (node (ref "R16") (pin "2") (pinfunction "2_2") (pintype "passive"))
    )
    (net (code "56") (name "Net-(JP2-Pad1)") (class "Default")
      (node (ref "JP2") (pin "1") (pinfunction "1_1") (pintype "passive"))
      (node (ref "R1") (pin "2") (pinfunction "2_2") (pintype "passive"))
    )
    (net (code "57") (name "Net-(JP10-Pad3)") (class "Default")
      (node (ref "JP10") (pin "3") (pinfunction "3_3") (pintype "passive"))
      (node (ref "U$1") (pin "VCC$2") (pinfunction "VCC$2_VCC$2") (pintype "power_in"))
    )
    (net (code "58") (name "Net-(JP10-Pad4)") (class "Default")
      (node (ref "JP10") (pin "4") (pinfunction "4_4") (pintype "passive"))
      (node (ref "U$1") (pin "RX1$2") (pinfunction "RX1$2_RX1$2") (pintype "bidirectional"))
    )
    (net (code "59") (name "Net-(JP10-Pad5)") (class "Default")
      (node (ref "JP10") (pin "5") (pinfunction "5_5") (pintype "passive"))
      (node (ref "U$1") (pin "TX0$2") (pinfunction "TX0$2_TX0$2") (pintype "bidirectional"))
    )
    (net (code "60") (name "Net-(JP10-Pad6)") (class "Default")
      (node (ref "JP10") (pin "6") (pinfunction "6_6") (pintype "passive"))
      (node (ref "U$1") (pin "DTR") (pinfunction "DTR_DTR") (pintype "input"))
    )
    (net (code "61") (name "Net-(R4-Pad1)") (class "Default")
      (node (ref "R4") (pin "1") (pinfunction "1_1") (pintype "passive"))
      (node (ref "U$1") (pin "D11") (pinfunction "D11_D11") (pintype "bidirectional"))
    )
    (net (code "62") (name "Net-(R5-Pad1)") (class "Default")
      (node (ref "R5") (pin "1") (pinfunction "1_1") (pintype "passive"))
      (node (ref "U$1") (pin "D10") (pinfunction "D10_D10") (pintype "bidirectional"))
    )
    (net (code "63") (name "Net-(R6-Pad2)") (class "Default")
      (node (ref "R6") (pin "2") (pinfunction "2_2") (pintype "passive"))
      (node (ref "U$1") (pin "D9") (pinfunction "D9_D9") (pintype "bidirectional"))
    )
    (net (code "64") (name "Net-(R7-Pad2)") (class "Default")
      (node (ref "R7") (pin "2") (pinfunction "2_2") (pintype "passive"))
      (node (ref "U$1") (pin "D8") (pinfunction "D8_D8") (pintype "bidirectional"))
    )
    (net (code "65") (name "Net-(R8-Pad2)") (class "Default")
      (node (ref "R8") (pin "2") (pinfunction "2_2") (pintype "passive"))
      (node (ref "U$1") (pin "D7") (pinfunction "D7_D7") (pintype "bidirectional"))
    )
    (net (code "66") (name "Net-(R9-Pad1)") (class "Default")
      (node (ref "R9") (pin "1") (pinfunction "1_1") (pintype "passive"))
      (node (ref "U$1") (pin "D6") (pinfunction "D6_D6") (pintype "bidirectional"))
    )
    (net (code "67") (name "Net-(R13-Pad1)") (class "Default")
      (node (ref "R13") (pin "1") (pinfunction "1_1") (pintype "passive"))
      (node (ref "U$1") (pin "D12") (pinfunction "D12_D12") (pintype "bidirectional"))
    )
    (net (code "68") (name "Net-(R20-Pad1)") (class "Default")
      (node (ref "R20") (pin "1") (pinfunction "1_1") (pintype "passive"))
      (node (ref "T3") (pin "B") (pinfunction "B_B") (pintype "passive"))
    )
    (net (code "69") (name "Net-(R22-Pad2)") (class "Default")
      (node (ref "R22") (pin "2") (pinfunction "2_2") (pintype "passive"))
      (node (ref "T3") (pin "C") (pinfunction "C_C") (pintype "passive"))
    )
    (net (code "70") (name "Net-(R25-Pad1)") (class "Default")
      (node (ref "R25") (pin "1") (pinfunction "1_1") (pintype "passive"))
      (node (ref "T4") (pin "B") (pinfunction "B_B") (pintype "passive"))
    )
    (net (code "71") (name "Net-(R27-Pad2)") (class "Default")
      (node (ref "R27") (pin "2") (pinfunction "2_2") (pintype "passive"))
      (node (ref "T4") (pin "C") (pinfunction "C_C") (pintype "passive"))
    )
    (net (code "72") (name "VDD") (class "Default")
      (node (ref "C1") (pin "+") (pinfunction "+_+") (pintype "passive"))
      (node (ref "C10") (pin "1") (pinfunction "1_1") (pintype "passive"))
      (node (ref "C12") (pin "1") (pinfunction "1_1") (pintype "passive"))
      (node (ref "C13") (pin "1") (pinfunction "1_1") (pintype "passive"))
      (node (ref "C2") (pin "+") (pinfunction "+_+") (pintype "passive"))
      (node (ref "C3") (pin "1") (pinfunction "1_1") (pintype "passive"))
      (node (ref "C4") (pin "1") (pinfunction "1_1") (pintype "passive"))
      (node (ref "C8") (pin "1") (pinfunction "1_1") (pintype "passive"))
      (node (ref "C9") (pin "1") (pinfunction "1_1") (pintype "passive"))
      (node (ref "JP3") (pin "1") (pinfunction "1_1") (pintype "passive"))
      (node (ref "JP4") (pin "1") (pinfunction "1_1") (pintype "passive"))
      (node (ref "L1") (pin "2") (pinfunction "2_2") (pintype "passive"))
      (node (ref "R14") (pin "1") (pinfunction "1_1") (pintype "passive"))
      (node (ref "R19") (pin "2") (pinfunction "2_2") (pintype "passive"))
      (node (ref "R24") (pin "2") (pinfunction "2_2") (pintype "passive"))
      (node (ref "R3") (pin "1") (pinfunction "1_1") (pintype "passive"))
      (node (ref "SG3") (pin "-") (pinfunction "2_-") (pintype "passive"))
      (node (ref "T1") (pin "C") (pinfunction "C_C") (pintype "passive"))
      (node (ref "T2") (pin "C") (pinfunction "C_C") (pintype "passive"))
      (node (ref "T5") (pin "C") (pinfunction "C_C") (pintype "passive"))
      (node (ref "U$1") (pin "RAW") (pinfunction "RAW_RAW") (pintype "power_in"))
    )
    (net (code "73") (name "VSS") (class "Default")
      (node (ref "C1") (pin "-") (pinfunction "-_-") (pintype "passive"))
      (node (ref "C10") (pin "2") (pinfunction "2_2") (pintype "passive"))
      (node (ref "C12") (pin "2") (pinfunction "2_2") (pintype "passive"))
      (node (ref "C13") (pin "2") (pinfunction "2_2") (pintype "passive"))
      (node (ref "C2") (pin "-") (pinfunction "-_-") (pintype "passive"))
      (node (ref "C3") (pin "2") (pinfunction "2_2") (pintype "passive"))
      (node (ref "C4") (pin "2") (pinfunction "2_2") (pintype "passive"))
      (node (ref "C8") (pin "2") (pinfunction "2_2") (pintype "passive"))
      (node (ref "C9") (pin "2") (pinfunction "2_2") (pintype "passive"))
      (node (ref "IC1") (pin "2") (pinfunction "A_2") (pintype "passive"))
      (node (ref "J1") (pin "2") (pinfunction "2_2") (pintype "passive"))
      (node (ref "J1") (pin "3") (pinfunction "3_3") (pintype "passive"))
      (node (ref "JP1") (pin "3") (pinfunction "3_3") (pintype "passive"))
      (node (ref "JP10") (pin "1") (pinfunction "1_1") (pintype "passive"))
      (node (ref "JP10") (pin "2") (pinfunction "2_2") (pintype "passive"))
      (node (ref "JP11") (pin "1") (pinfunction "1_1") (pintype "passive"))
      (node (ref "JP12") (pin "1") (pinfunction "1_1") (pintype "passive"))
      (node (ref "JP13") (pin "1") (pinfunction "1_1") (pintype "passive"))
      (node (ref "JP14") (pin "1") (pinfunction "1_1") (pintype "passive"))
      (node (ref "JP15") (pin "1") (pinfunction "1_1") (pintype "passive"))
      (node (ref "JP16") (pin "1") (pinfunction "1_1") (pintype "passive"))
      (node (ref "JP17") (pin "1") (pinfunction "1_1") (pintype "passive"))
      (node (ref "JP2") (pin "3") (pinfunction "3_3") (pintype "passive"))
      (node (ref "JP3") (pin "2") (pinfunction "2_2") (pintype "passive"))
      (node (ref "JP4") (pin "2") (pinfunction "2_2") (pintype "passive"))
      (node (ref "JP7") (pin "5") (pinfunction "5_5") (pintype "passive"))
      (node (ref "JP8") (pin "1") (pinfunction "1_1") (pintype "passive"))
      (node (ref "JP9") (pin "1") (pinfunction "1_1") (pintype "passive"))
      (node (ref "R10") (pin "1") (pinfunction "1_1") (pintype "passive"))
      (node (ref "R11") (pin "1") (pinfunction "1_1") (pintype "passive"))
      (node (ref "R12") (pin "1") (pinfunction "1_1") (pintype "passive"))
      (node (ref "R21") (pin "2") (pinfunction "2_2") (pintype "passive"))
      (node (ref "R26") (pin "2") (pinfunction "2_2") (pintype "passive"))
      (node (ref "T3") (pin "E") (pinfunction "E_E") (pintype "passive"))
      (node (ref "T4") (pin "E") (pinfunction "E_E") (pintype "passive"))
      (node (ref "U$1") (pin "GDN$1") (pinfunction "GND$1_GDN$1") (pintype "power_in"))
      (node (ref "U$1") (pin "GND$2") (pinfunction "GND$2_GND$2") (pintype "power_in"))
      (node (ref "U$1") (pin "GND$3") (pinfunction "GND$3_GND$3") (pintype "power_in"))
      (node (ref "U$1") (pin "GND$4") (pinfunction "GND$4_GND$4") (pintype "power_in"))
    )
    (net (code "74") (name "unconnected-(IC4C-A-Pad8)") (class "Default")
      (node (ref "IC4") (pin "8") (pinfunction "A_8") (pintype "tri_state"))
    )
    (net (code "75") (name "unconnected-(IC4C-B-Pad9)") (class "Default")
      (node (ref "IC4") (pin "9") (pinfunction "B_9") (pintype "tri_state"))
    )
    (net (code "76") (name "unconnected-(IC4C-C-Pad6)") (class "Default")
      (node (ref "IC4") (pin "6") (pinfunction "C_6") (pintype "input"))
    )
    (net (code "77") (name "unconnected-(IC4D-A-Pad11)") (class "Default")
      (node (ref "IC4") (pin "11") (pinfunction "A_11") (pintype "tri_state"))
    )
    (net (code "78") (name "unconnected-(IC4D-B-Pad10)") (class "Default")
      (node (ref "IC4") (pin "10") (pinfunction "B_10") (pintype "tri_state"))
    )
    (net (code "79") (name "unconnected-(IC4D-C-Pad12)") (class "Default")
      (node (ref "IC4") (pin "12") (pinfunction "C_12") (pintype "input"))
    )
    (net (code "80") (name "unconnected-(U$1-PadA2)") (class "Default")
      (node (ref "U$1") (pin "A2") (pinfunction "A2_A2") (pintype "bidirectional"))
    )
    (net (code "81") (name "unconnected-(U$1-PadA3)") (class "Default")
      (node (ref "U$1") (pin "A3") (pinfunction "A3_A3") (pintype "bidirectional"))
    )
    (net (code "82") (name "unconnected-(U$1-PadA4)") (class "Default")
      (node (ref "U$1") (pin "A4") (pinfunction "A4_A4") (pintype "bidirectional"))
    )
    (net (code "83") (name "unconnected-(U$1-PadA5)") (class "Default")
      (node (ref "U$1") (pin "A5") (pinfunction "A5_A5") (pintype "bidirectional"))
    )
    (net (code "84") (name "unconnected-(U$1-PadA6)") (class "Default")
      (node (ref "U$1") (pin "A6") (pinfunction "A6_A6") (pintype "input"))
    )
    (net (code "85") (name "unconnected-(U$1-PadA7)") (class "Default")
      (node (ref "U$1") (pin "A7") (pinfunction "A7_A7") (pintype "input"))
    )
    (net (code "86") (name "unconnected-(U$1-PadD13)") (class "Default")
      (node (ref "U$1") (pin "D13") (pinfunction "D13_D13") (pintype "bidirectional"))
    )
    (net (code "87") (name "unconnected-(U$1-PadRST$1)") (class "Default")
      (node (ref "U$1") (pin "RST$1") (pinfunction "RST$1_RST$1") (pintype "input"))
    )
    (net (code "88") (name "unconnected-(U$1-PadRST$2)") (class "Default")
      (node (ref "U$1") (pin "RST$2") (pinfunction "RST$2_RST$2") (pintype "input"))
    )
    (net (code "89") (name "unconnected-(U$1-PadRX1$1)") (class "Default")
      (node (ref "U$1") (pin "RX1$1") (pinfunction "RX1$1_RX1$1") (pintype "bidirectional"))
    )
    (net (code "90") (name "unconnected-(U$1-PadTX0$1)") (class "Default")
      (node (ref "U$1") (pin "TX0$1") (pinfunction "TX0$1_TX0$1") (pintype "bidirectional"))
    )
  )
)
